# KlokWave_Klok.net
KiCad netlist of a schematic drawn in Altium Designer
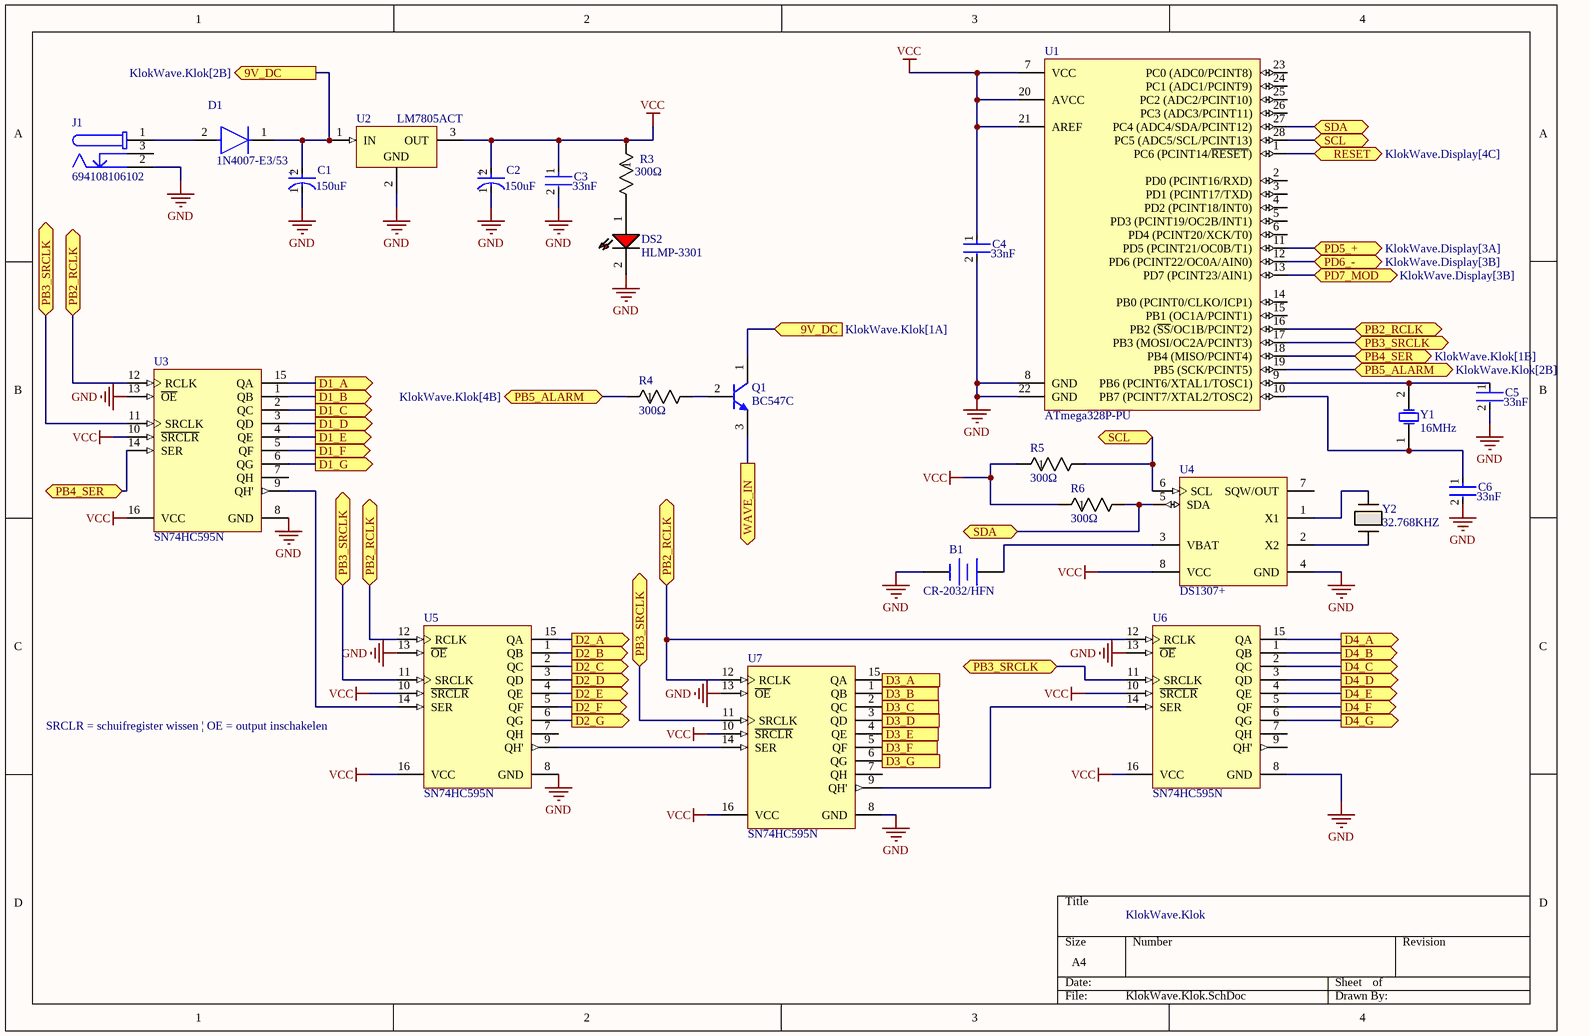
[diagram p0: KlokWave.Klok.SchDoc]

(export (version "E")
  (design (tool "Eeschema 10.0.6"))
  (components
    (comp (ref "B1")
      (value "CR-2032/HFN")
      (footprint "THT 3VBAT: PANA-CR-2032HFN")
      (description "Coin Cell Battery, 225 mAh, 0.2 mA, 3 V, -30 to 60 degC, Bulk")
      (fields (field (name "MANUFACTURER") "Panasonic"))
      (libsource (lib "KlokWave") (part "CMP-2000-05296-1"))
    )
    (comp (ref "C1")
      (value "16SEPC150MD")
      (footprint "THT PolCondensator FP-OS-CON-TH-E7-d_0_45-MFG")
      (description "Conductive Polymer Aluminum Solid Capacitors (OS-CON) 150uF ±20% 16V RADIAL TH 8x7mm")
      (fields
        (field (name "VOLTAGE") "16V")
        (field (name "TOLERANCE") "20%")
        (field (name "CAPACITANCE") "150uF")
      )
      (libsource (lib "KlokWave") (part "CMP-05428-000489-1"))
    )
    (comp (ref "C2")
      (value "16SEPC150MD")
      (footprint "THT PolCondensator FP-OS-CON-TH-E7-d_0_45-MFG")
      (description "Conductive Polymer Aluminum Solid Capacitors (OS-CON) 150uF ±20% 16V RADIAL TH 8x7mm")
      (fields
        (field (name "VOLTAGE") "16V")
        (field (name "TOLERANCE") "20%")
        (field (name "CAPACITANCE") "150uF")
      )
      (libsource (lib "KlokWave") (part "CMP-05428-000489-1"))
    )
    (comp (ref "C3")
      (value "565R30GASS33")
      (footprint "THT NonPol CerCOndensator: FP-565R30GASS33-MFG")
      (description "565R30GASS33 33nF 3 kV dc THT Ceramic Single Layer Capacitor; Z5U Dielectric Radial 565R Series")
      (fields
        (field (name "VOLTAGE") "3kV")
        (field (name "TOLERANCE") "20%")
        (field (name "CAPACITANCE") "33nF")
      )
      (libsource (lib "KlokWave") (part "CMP-00030-41968055-1"))
    )
    (comp (ref "C4")
      (value "565R30GASS33")
      (footprint "THT NonPol CerCOndensator: FP-565R30GASS33-MFG")
      (description "565R30GASS33 33nF 3 kV dc THT Ceramic Single Layer Capacitor; Z5U Dielectric Radial 565R Series")
      (fields
        (field (name "VOLTAGE") "3kV")
        (field (name "TOLERANCE") "20%")
        (field (name "CAPACITANCE") "33nF")
      )
      (libsource (lib "KlokWave") (part "CMP-00030-41968055-1"))
    )
    (comp (ref "C5")
      (value "565R30GASS33")
      (footprint "THT NonPol CerCOndensator: FP-565R30GASS33-MFG")
      (description "565R30GASS33 33nF 3 kV dc THT Ceramic Single Layer Capacitor; Z5U Dielectric Radial 565R Series")
      (fields
        (field (name "VOLTAGE") "3kV")
        (field (name "TOLERANCE") "20%")
        (field (name "CAPACITANCE") "33nF")
      )
      (libsource (lib "KlokWave") (part "CMP-00030-41968055-1"))
    )
    (comp (ref "C6")
      (value "565R30GASS33")
      (footprint "THT NonPol CerCOndensator: FP-565R30GASS33-MFG")
      (description "565R30GASS33 33nF 3 kV dc THT Ceramic Single Layer Capacitor; Z5U Dielectric Radial 565R Series")
      (fields
        (field (name "VOLTAGE") "3kV")
        (field (name "TOLERANCE") "20%")
        (field (name "CAPACITANCE") "33nF")
      )
      (libsource (lib "KlokWave") (part "CMP-00030-41968055-1"))
    )
    (comp (ref "D1")
      (value "1N4007-E3/53")
      (footprint "THT Diode FP-1N4007-E3-53-MFG")
      (description "1N4007 DIODE GEN PURP 1KV 1A DO204AL")
      (libsource (lib "KlokWave") (part "CMP-02540-000066-1"))
    )
    (comp (ref "DS2")
      (value "HLMP-3301")
      (footprint "THT LED: AVAG-HLMP-3301-2")
      (description "T-1 3/4 (5 mm) Diffused LED Lamp, 1.9 V, -40 to 100 degC, 2-Pin THD")
      (fields (field (name "MANUFACTURER") "Avago"))
      (libsource (lib "KlokWave") (part "CMP-2000-06411-1"))
    )
    (comp (ref "J1")
      (value "694108106102")
      (footprint "THT DC Power Jack: 694106301002")
      (description "DC Power JAck")
      (libsource (lib "KlokWave") (part "CMP-1502-00180-2"))
    )
    (comp (ref "Q1")
      (value "BC547C")
      (footprint "THT NPN Transistor: ONSC-TO-92-3-29-11_AM_BL")
      (description "BC547C: THT Amplifier Transistor, NPN Silicon, 3-Pin TO-92, Bulk Box")
      (fields (field (name "MANUFACTURER") "On Semiconductor"))
      (libsource (lib "KlokWave") (part "CMP-1048-01437-1"))
    )
    (comp (ref "R3")
      (value "AC03000003000JAC00")
      (footprint "THT Resistor: RES_AC03_VIS")
      (description "AC03000003000JAC00 Res Wirewound THT")
      (fields (field (name "TOLERANCE") "5%") (field (name "RESISTANCE") "300Ω"))
      (libsource (lib "KlokWave") (part "CMP-00030-39746760-1"))
    )
    (comp (ref "R4")
      (value "AC03000003000JAC00")
      (footprint "THT Resistor: RES_AC03_VIS")
      (description "AC03000003000JAC00 Res Wirewound THT")
      (fields (field (name "TOLERANCE") "5%") (field (name "RESISTANCE") "300Ω"))
      (libsource (lib "KlokWave") (part "CMP-00030-39746760-1"))
    )
    (comp (ref "R5")
      (value "AC03000003000JAC00")
      (footprint "THT Resistor: RES_AC03_VIS")
      (description "AC03000003000JAC00 Res Wirewound THT")
      (fields (field (name "TOLERANCE") "5%") (field (name "RESISTANCE") "300Ω"))
      (libsource (lib "KlokWave") (part "CMP-00030-39746760-1"))
    )
    (comp (ref "R6")
      (value "AC03000003000JAC00")
      (footprint "THT Resistor: RES_AC03_VIS")
      (description "AC03000003000JAC00 Res Wirewound THT")
      (fields (field (name "TOLERANCE") "5%") (field (name "RESISTANCE") "300Ω"))
      (libsource (lib "KlokWave") (part "CMP-00030-39746760-1"))
    )
    (comp (ref "U1")
      (value "ATmega328P-PU")
      (footprint "THT ATMEGA328P-PU: 28P3")
      (libsource (lib "KlokWave") (part "CMP-0095-00013-2"))
    )
    (comp (ref "U2")
      (value "LM7805ACT")
      (footprint "THT LM7805: FAIR-TO-220-3")
      (description "Positive Voltage Regulator, 5 V, 1 A, 0 to 125 degC, 3-Pin TO-220, RoHS, Tube")
      (fields (field (name "MANUFACTURER") "Fairchild"))
      (libsource (lib "KlokWave") (part "CMP-2000-04937-1"))
    )
    (comp (ref "U3")
      (value "SN74HC595N")
      (footprint "THT 74HC595N: N0016A")
      (description "8-Bit Shift Registers With 3-State Output Registers, N0016A, TUBE")
      (fields
        (field (name "GENERIC PART NUMBER") "SN74HC595")
        (field (name "MANUFACTURER") "Texas Instruments")
      )
      (libsource (lib "KlokWave") (part "CMP-0780-00137-3"))
    )
    (comp (ref "U4")
      (value "DS1307+")
      (footprint "THT Chip DS1307: P8+2")
      (description "64 x 8, Serial, I2C Real-Time Clock, 5.0V, 8-Pin PDIP, 0 to 70 degC, Pb-Free")
      (libsource (lib "KlokWave") (part "CMP-0254-00152-1"))
    )
    (comp (ref "U5")
      (value "SN74HC595N")
      (footprint "THT 74HC595N: N0016A")
      (description "8-Bit Shift Registers With 3-State Output Registers, N0016A, TUBE")
      (fields
        (field (name "GENERIC PART NUMBER") "SN74HC595")
        (field (name "MANUFACTURER") "Texas Instruments")
      )
      (libsource (lib "KlokWave") (part "CMP-0780-00137-3"))
    )
    (comp (ref "U6")
      (value "SN74HC595N")
      (footprint "THT 74HC595N: N0016A")
      (description "8-Bit Shift Registers With 3-State Output Registers, N0016A, TUBE")
      (fields
        (field (name "GENERIC PART NUMBER") "SN74HC595")
        (field (name "MANUFACTURER") "Texas Instruments")
      )
      (libsource (lib "KlokWave") (part "CMP-0780-00137-3"))
    )
    (comp (ref "U7")
      (value "SN74HC595N")
      (footprint "THT 74HC595N: N0016A")
      (description "8-Bit Shift Registers With 3-State Output Registers, N0016A, TUBE")
      (fields
        (field (name "GENERIC PART NUMBER") "SN74HC595")
        (field (name "MANUFACTURER") "Texas Instruments")
      )
      (libsource (lib "KlokWave") (part "CMP-0780-00137-3"))
    )
    (comp (ref "Y1")
      (value "16MHz")
      (footprint "THT 16 MHz: WE-XTAL_HC49/4H")
      (description "THT Quartz Crystal, HC49/4H, 16MHz, +/-30ppm WE-XTAL")
      (fields
        (field (name "MANUFACTURER PART NUMBER") "830003240B")
        (field (name "MANUFACTURER") "Wurth Elektronik")
      )
      (libsource (lib "KlokWave") (part "830003240B"))
    )
    (comp (ref "Y2")
      (value "32.768KHZ")
      (footprint "THT 32 KHz OSC: XTAL_AB38T_ABR")
      (description "THT CRYSTAL 32.7680KHZ 12.5PF TH")
      (libsource (lib "KlokWave") (part "AB38T-32.768KHZ"))
    )
  )
  (nets
    (net (code "1") (name "/9V_DC") (class "Default")
      (node (ref "C1") (pin "2") (pinfunction "A_2") (pintype "passive"))
      (node (ref "D1") (pin "1") (pinfunction "C_1") (pintype "passive"))
      (node (ref "Q1") (pin "1") (pinfunction "C_1") (pintype "passive"))
      (node (ref "U2") (pin "1") (pinfunction "IN_1") (pintype "input"))
    )
    (net (code "2") (name "/D1_A") (class "Default")
      (node (ref "U3") (pin "15") (pinfunction "QA_15") (pintype "tri_state"))
    )
    (net (code "3") (name "/D1_B") (class "Default")
      (node (ref "U3") (pin "1") (pinfunction "QB_1") (pintype "tri_state"))
    )
    (net (code "4") (name "/D1_C") (class "Default")
      (node (ref "U3") (pin "2") (pinfunction "QC_2") (pintype "tri_state"))
    )
    (net (code "5") (name "/D1_D") (class "Default")
      (node (ref "U3") (pin "3") (pinfunction "QD_3") (pintype "tri_state"))
    )
    (net (code "6") (name "/D1_E") (class "Default")
      (node (ref "U3") (pin "4") (pinfunction "QE_4") (pintype "tri_state"))
    )
    (net (code "7") (name "/D1_F") (class "Default")
      (node (ref "U3") (pin "5") (pinfunction "QF_5") (pintype "tri_state"))
    )
    (net (code "8") (name "/D1_G") (class "Default")
      (node (ref "U3") (pin "6") (pinfunction "QG_6") (pintype "tri_state"))
    )
    (net (code "9") (name "/D2_A") (class "Default")
      (node (ref "U5") (pin "15") (pinfunction "QA_15") (pintype "tri_state"))
    )
    (net (code "10") (name "/D2_B") (class "Default")
      (node (ref "U5") (pin "1") (pinfunction "QB_1") (pintype "tri_state"))
    )
    (net (code "11") (name "/D2_C") (class "Default")
      (node (ref "U5") (pin "2") (pinfunction "QC_2") (pintype "tri_state"))
    )
    (net (code "12") (name "/D2_D") (class "Default")
      (node (ref "U5") (pin "3") (pinfunction "QD_3") (pintype "tri_state"))
    )
    (net (code "13") (name "/D2_E") (class "Default")
      (node (ref "U5") (pin "4") (pinfunction "QE_4") (pintype "tri_state"))
    )
    (net (code "14") (name "/D2_F") (class "Default")
      (node (ref "U5") (pin "5") (pinfunction "QF_5") (pintype "tri_state"))
    )
    (net (code "15") (name "/D2_G") (class "Default")
      (node (ref "U5") (pin "6") (pinfunction "QG_6") (pintype "tri_state"))
    )
    (net (code "16") (name "/D3_A") (class "Default")
      (node (ref "U7") (pin "15") (pinfunction "QA_15") (pintype "tri_state"))
    )
    (net (code "17") (name "/D3_B") (class "Default")
      (node (ref "U7") (pin "1") (pinfunction "QB_1") (pintype "tri_state"))
    )
    (net (code "18") (name "/D3_C") (class "Default")
      (node (ref "U7") (pin "2") (pinfunction "QC_2") (pintype "tri_state"))
    )
    (net (code "19") (name "/D3_D") (class "Default")
      (node (ref "U7") (pin "3") (pinfunction "QD_3") (pintype "tri_state"))
    )
    (net (code "20") (name "/D3_E") (class "Default")
      (node (ref "U7") (pin "4") (pinfunction "QE_4") (pintype "tri_state"))
    )
    (net (code "21") (name "/D3_F") (class "Default")
      (node (ref "U7") (pin "5") (pinfunction "QF_5") (pintype "tri_state"))
    )
    (net (code "22") (name "/D3_G") (class "Default")
      (node (ref "U7") (pin "6") (pinfunction "QG_6") (pintype "tri_state"))
    )
    (net (code "23") (name "/D4_A") (class "Default")
      (node (ref "U6") (pin "15") (pinfunction "QA_15") (pintype "tri_state"))
    )
    (net (code "24") (name "/D4_B") (class "Default")
      (node (ref "U6") (pin "1") (pinfunction "QB_1") (pintype "tri_state"))
    )
    (net (code "25") (name "/D4_C") (class "Default")
      (node (ref "U6") (pin "2") (pinfunction "QC_2") (pintype "tri_state"))
    )
    (net (code "26") (name "/D4_D") (class "Default")
      (node (ref "U6") (pin "3") (pinfunction "QD_3") (pintype "tri_state"))
    )
    (net (code "27") (name "/D4_E") (class "Default")
      (node (ref "U6") (pin "4") (pinfunction "QE_4") (pintype "tri_state"))
    )
    (net (code "28") (name "/D4_F") (class "Default")
      (node (ref "U6") (pin "5") (pinfunction "QF_5") (pintype "tri_state"))
    )
    (net (code "29") (name "/D4_G") (class "Default")
      (node (ref "U6") (pin "6") (pinfunction "QG_6") (pintype "tri_state"))
    )
    (net (code "30") (name "/PB2_RCLK") (class "Default")
      (node (ref "U1") (pin "16") (pinfunction "PB2_(~{SS}/OC1B/PCINT2)_16") (pintype "bidirectional"))
      (node (ref "U3") (pin "12") (pinfunction "RCLK_12") (pintype "input"))
      (node (ref "U5") (pin "12") (pinfunction "RCLK_12") (pintype "input"))
      (node (ref "U6") (pin "12") (pinfunction "RCLK_12") (pintype "input"))
      (node (ref "U7") (pin "12") (pinfunction "RCLK_12") (pintype "input"))
    )
    (net (code "31") (name "/PB3_SRCLK") (class "Default")
      (node (ref "U1") (pin "17") (pinfunction "PB3_(MOSI/OC2A/PCINT3)_17") (pintype "bidirectional"))
      (node (ref "U3") (pin "11") (pinfunction "SRCLK_11") (pintype "input"))
      (node (ref "U5") (pin "11") (pinfunction "SRCLK_11") (pintype "input"))
      (node (ref "U6") (pin "11") (pinfunction "SRCLK_11") (pintype "input"))
      (node (ref "U7") (pin "11") (pinfunction "SRCLK_11") (pintype "input"))
    )
    (net (code "32") (name "/PB4_SER") (class "Default")
      (node (ref "U1") (pin "18") (pinfunction "PB4_(MISO/PCINT4)_18") (pintype "bidirectional"))
      (node (ref "U3") (pin "14") (pinfunction "SER_14") (pintype "input"))
    )
    (net (code "33") (name "/PB5_ALARM") (class "Default")
      (node (ref "R4") (pin "1") (pinfunction "1_1") (pintype "passive"))
      (node (ref "U1") (pin "19") (pinfunction "PB5_(SCK/PCINT5)_19") (pintype "bidirectional"))
    )
    (net (code "34") (name "/PD5_+") (class "Default")
      (node (ref "U1") (pin "11") (pinfunction "PD5_(PCINT21/OC0B/T1)_11") (pintype "bidirectional"))
    )
    (net (code "35") (name "/PD6_-") (class "Default")
      (node (ref "U1") (pin "12") (pinfunction "PD6_(PCINT22/OC0A/AIN0)_12") (pintype "bidirectional"))
    )
    (net (code "36") (name "/PD7_MOD") (class "Default")
      (node (ref "U1") (pin "13") (pinfunction "PD7_(PCINT23/AIN1)_13") (pintype "bidirectional"))
    )
    (net (code "37") (name "/RESET") (class "Default")
      (node (ref "U1") (pin "1") (pinfunction "PC6_(PCINT14/~{RESET})_1") (pintype "bidirectional"))
    )
    (net (code "38") (name "/SCL") (class "Default")
      (node (ref "R5") (pin "2") (pinfunction "2_2") (pintype "passive"))
      (node (ref "U1") (pin "28") (pinfunction "PC5_(ADC5/SCL/PCINT13)_28") (pintype "bidirectional"))
      (node (ref "U4") (pin "6") (pinfunction "SCL_6") (pintype "input"))
    )
    (net (code "39") (name "/SDA") (class "Default")
      (node (ref "R6") (pin "2") (pinfunction "2_2") (pintype "passive"))
      (node (ref "U1") (pin "27") (pinfunction "PC4_(ADC4/SDA/PCINT12)_27") (pintype "bidirectional"))
      (node (ref "U4") (pin "5") (pinfunction "SDA_5") (pintype "bidirectional"))
    )
    (net (code "40") (name "/WAVE_IN") (class "Default")
      (node (ref "Q1") (pin "3") (pinfunction "E_3") (pintype "passive"))
    )
    (net (code "41") (name "GND") (class "Default")
      (node (ref "B1") (pin "2") (pinfunction "-_2") (pintype "passive"))
      (node (ref "C1") (pin "1") (pinfunction "C_1") (pintype "passive"))
      (node (ref "C2") (pin "1") (pinfunction "C_1") (pintype "passive"))
      (node (ref "C3") (pin "2") (pinfunction "2_2") (pintype "passive"))
      (node (ref "C4") (pin "2") (pinfunction "2_2") (pintype "passive"))
      (node (ref "C5") (pin "2") (pinfunction "2_2") (pintype "passive"))
      (node (ref "C6") (pin "2") (pinfunction "2_2") (pintype "passive"))
      (node (ref "DS2") (pin "2") (pinfunction "A_2") (pintype "passive"))
      (node (ref "J1") (pin "2") (pinfunction "2_2") (pintype "passive"))
      (node (ref "U1") (pin "22") (pinfunction "GND_22") (pintype "power_in"))
      (node (ref "U1") (pin "8") (pinfunction "GND_8") (pintype "power_in"))
      (node (ref "U2") (pin "2") (pinfunction "GND_2") (pintype "power_in"))
      (node (ref "U3") (pin "13") (pinfunction "~{OE}_13") (pintype "input"))
      (node (ref "U3") (pin "8") (pinfunction "GND_8") (pintype "power_in"))
      (node (ref "U4") (pin "4") (pinfunction "GND_4") (pintype "power_in"))
      (node (ref "U5") (pin "13") (pinfunction "~{OE}_13") (pintype "input"))
      (node (ref "U5") (pin "8") (pinfunction "GND_8") (pintype "power_in"))
      (node (ref "U6") (pin "13") (pinfunction "~{OE}_13") (pintype "input"))
      (node (ref "U6") (pin "8") (pinfunction "GND_8") (pintype "power_in"))
      (node (ref "U7") (pin "13") (pinfunction "~{OE}_13") (pintype "input"))
      (node (ref "U7") (pin "8") (pinfunction "GND_8") (pintype "power_in"))
    )
    (net (code "42") (name "Net-(B1-+)") (class "Default")
      (node (ref "B1") (pin "1") (pinfunction "+_1") (pintype "passive"))
      (node (ref "U4") (pin "3") (pinfunction "VBAT_3") (pintype "power_in"))
    )
    (net (code "43") (name "Net-(D1-A)") (class "Default")
      (node (ref "D1") (pin "2") (pinfunction "A_2") (pintype "passive"))
      (node (ref "J1") (pin "1") (pinfunction "1_1") (pintype "passive"))
    )
    (net (code "44") (name "Net-(DS2-K)") (class "Default")
      (node (ref "DS2") (pin "1") (pinfunction "K_1") (pintype "passive"))
      (node (ref "R3") (pin "2") (pinfunction "2_2") (pintype "passive"))
    )
    (net (code "45") (name "Net-(Q1-B)") (class "Default")
      (node (ref "Q1") (pin "2") (pinfunction "B_2") (pintype "passive"))
      (node (ref "R4") (pin "2") (pinfunction "2_2") (pintype "passive"))
    )
    (net (code "46") (name "Net-(U1-PB6_(PCINT6{slash}XTAL1{slash}TOSC1))") (class "Default")
      (node (ref "C5") (pin "1") (pinfunction "1_1") (pintype "passive"))
      (node (ref "U1") (pin "9") (pinfunction "PB6_(PCINT6/XTAL1/TOSC1)_9") (pintype "bidirectional"))
      (node (ref "Y1") (pin "2") (pinfunction "OSC2_2") (pintype "passive"))
    )
    (net (code "47") (name "Net-(U1-PB7_(PCINT7{slash}XTAL2{slash}TOSC2))") (class "Default")
      (node (ref "C6") (pin "1") (pinfunction "1_1") (pintype "passive"))
      (node (ref "U1") (pin "10") (pinfunction "PB7_(PCINT7/XTAL2/TOSC2)_10") (pintype "bidirectional"))
      (node (ref "Y1") (pin "1") (pinfunction "OSC1_1") (pintype "passive"))
    )
    (net (code "48") (name "Net-(U3-QH')") (class "Default")
      (node (ref "U3") (pin "9") (pinfunction "QH'_9") (pintype "output"))
      (node (ref "U5") (pin "14") (pinfunction "SER_14") (pintype "input"))
    )
    (net (code "49") (name "Net-(U4-X1)") (class "Default")
      (node (ref "U4") (pin "1") (pinfunction "X1_1") (pintype "passive"))
      (node (ref "Y2") (pin "1") (pinfunction "1_1") (pintype "passive"))
    )
    (net (code "50") (name "Net-(U4-X2)") (class "Default")
      (node (ref "U4") (pin "2") (pinfunction "X2_2") (pintype "passive"))
      (node (ref "Y2") (pin "2") (pinfunction "2_2") (pintype "passive"))
    )
    (net (code "51") (name "Net-(U5-QH')") (class "Default")
      (node (ref "U5") (pin "9") (pinfunction "QH'_9") (pintype "output"))
      (node (ref "U7") (pin "14") (pinfunction "SER_14") (pintype "input"))
    )
    (net (code "52") (name "Net-(U6-SER)") (class "Default")
      (node (ref "U6") (pin "14") (pinfunction "SER_14") (pintype "input"))
      (node (ref "U7") (pin "9") (pinfunction "QH'_9") (pintype "output"))
    )
    (net (code "53") (name "VCC") (class "Default")
      (node (ref "C2") (pin "2") (pinfunction "A_2") (pintype "passive"))
      (node (ref "C3") (pin "1") (pinfunction "1_1") (pintype "passive"))
      (node (ref "C4") (pin "1") (pinfunction "1_1") (pintype "passive"))
      (node (ref "R3") (pin "1") (pinfunction "1_1") (pintype "passive"))
      (node (ref "R5") (pin "1") (pinfunction "1_1") (pintype "passive"))
      (node (ref "R6") (pin "1") (pinfunction "1_1") (pintype "passive"))
      (node (ref "U1") (pin "20") (pinfunction "AVCC_20") (pintype "power_in"))
      (node (ref "U1") (pin "21") (pinfunction "AREF_21") (pintype "power_in"))
      (node (ref "U1") (pin "7") (pinfunction "VCC_7") (pintype "power_in"))
      (node (ref "U2") (pin "3") (pinfunction "OUT_3") (pintype "power_in"))
      (node (ref "U3") (pin "10") (pinfunction "~{SRCLR}_10") (pintype "input"))
      (node (ref "U3") (pin "16") (pinfunction "VCC_16") (pintype "power_in"))
      (node (ref "U4") (pin "8") (pinfunction "VCC_8") (pintype "power_in"))
      (node (ref "U5") (pin "10") (pinfunction "~{SRCLR}_10") (pintype "input"))
      (node (ref "U5") (pin "16") (pinfunction "VCC_16") (pintype "power_in"))
      (node (ref "U6") (pin "10") (pinfunction "~{SRCLR}_10") (pintype "input"))
      (node (ref "U6") (pin "16") (pinfunction "VCC_16") (pintype "power_in"))
      (node (ref "U7") (pin "10") (pinfunction "~{SRCLR}_10") (pintype "input"))
      (node (ref "U7") (pin "16") (pinfunction "VCC_16") (pintype "power_in"))
    )
    (net (code "54") (name "unconnected-(J1-Pad3)") (class "Default")
      (node (ref "J1") (pin "3") (pinfunction "3_3") (pintype "passive"))
    )
    (net (code "55") (name "unconnected-(U1-PB0_(PCINT0{slash}CLKO{slash}ICP1)-Pad14)") (class "Default")
      (node (ref "U1") (pin "14") (pinfunction "PB0_(PCINT0/CLKO/ICP1)_14") (pintype "bidirectional"))
    )
    (net (code "56") (name "unconnected-(U1-PB1_(OC1A{slash}PCINT1)-Pad15)") (class "Default")
      (node (ref "U1") (pin "15") (pinfunction "PB1_(OC1A/PCINT1)_15") (pintype "bidirectional"))
    )
    (net (code "57") (name "unconnected-(U1-PC0_(ADC0{slash}PCINT8)-Pad23)") (class "Default")
      (node (ref "U1") (pin "23") (pinfunction "PC0_(ADC0/PCINT8)_23") (pintype "bidirectional"))
    )
    (net (code "58") (name "unconnected-(U1-PC1_(ADC1{slash}PCINT9)-Pad24)") (class "Default")
      (node (ref "U1") (pin "24") (pinfunction "PC1_(ADC1/PCINT9)_24") (pintype "bidirectional"))
    )
    (net (code "59") (name "unconnected-(U1-PC2_(ADC2{slash}PCINT10)-Pad25)") (class "Default")
      (node (ref "U1") (pin "25") (pinfunction "PC2_(ADC2/PCINT10)_25") (pintype "bidirectional"))
    )
    (net (code "60") (name "unconnected-(U1-PC3_(ADC3{slash}PCINT11)-Pad26)") (class "Default")
      (node (ref "U1") (pin "26") (pinfunction "PC3_(ADC3/PCINT11)_26") (pintype "bidirectional"))
    )
    (net (code "61") (name "unconnected-(U1-PD0_(PCINT16{slash}RXD)-Pad2)") (class "Default")
      (node (ref "U1") (pin "2") (pinfunction "PD0_(PCINT16/RXD)_2") (pintype "bidirectional"))
    )
    (net (code "62") (name "unconnected-(U1-PD1_(PCINT17{slash}TXD)-Pad3)") (class "Default")
      (node (ref "U1") (pin "3") (pinfunction "PD1_(PCINT17/TXD)_3") (pintype "bidirectional"))
    )
    (net (code "63") (name "unconnected-(U1-PD2_(PCINT18{slash}INT0)-Pad4)") (class "Default")
      (node (ref "U1") (pin "4") (pinfunction "PD2_(PCINT18/INT0)_4") (pintype "bidirectional"))
    )
    (net (code "64") (name "unconnected-(U1-PD3_(PCINT19{slash}OC2B{slash}INT1)-Pad5)") (class "Default")
      (node (ref "U1") (pin "5") (pinfunction "PD3_(PCINT19/OC2B/INT1)_5") (pintype "bidirectional"))
    )
    (net (code "65") (name "unconnected-(U1-PD4_(PCINT20{slash}XCK{slash}T0)-Pad6)") (class "Default")
      (node (ref "U1") (pin "6") (pinfunction "PD4_(PCINT20/XCK/T0)_6") (pintype "bidirectional"))
    )
    (net (code "66") (name "unconnected-(U3-QH-Pad7)") (class "Default")
      (node (ref "U3") (pin "7") (pinfunction "QH_7") (pintype "tri_state"))
    )
    (net (code "67") (name "unconnected-(U4-SQW{slash}OUT-Pad7)") (class "Default")
      (node (ref "U4") (pin "7") (pinfunction "SQW/OUT_7") (pintype "open_collector"))
    )
    (net (code "68") (name "unconnected-(U5-QH-Pad7)") (class "Default")
      (node (ref "U5") (pin "7") (pinfunction "QH_7") (pintype "tri_state"))
    )
    (net (code "69") (name "unconnected-(U6-QH'-Pad9)") (class "Default")
      (node (ref "U6") (pin "9") (pinfunction "QH'_9") (pintype "output"))
    )
    (net (code "70") (name "unconnected-(U6-QH-Pad7)") (class "Default")
      (node (ref "U6") (pin "7") (pinfunction "QH_7") (pintype "tri_state"))
    )
    (net (code "71") (name "unconnected-(U7-QH-Pad7)") (class "Default")
      (node (ref "U7") (pin "7") (pinfunction "QH_7") (pintype "tri_state"))
    )
  )
)
